# wfp_connector.net
KiCad netlist of a schematic drawn in Altium Designer
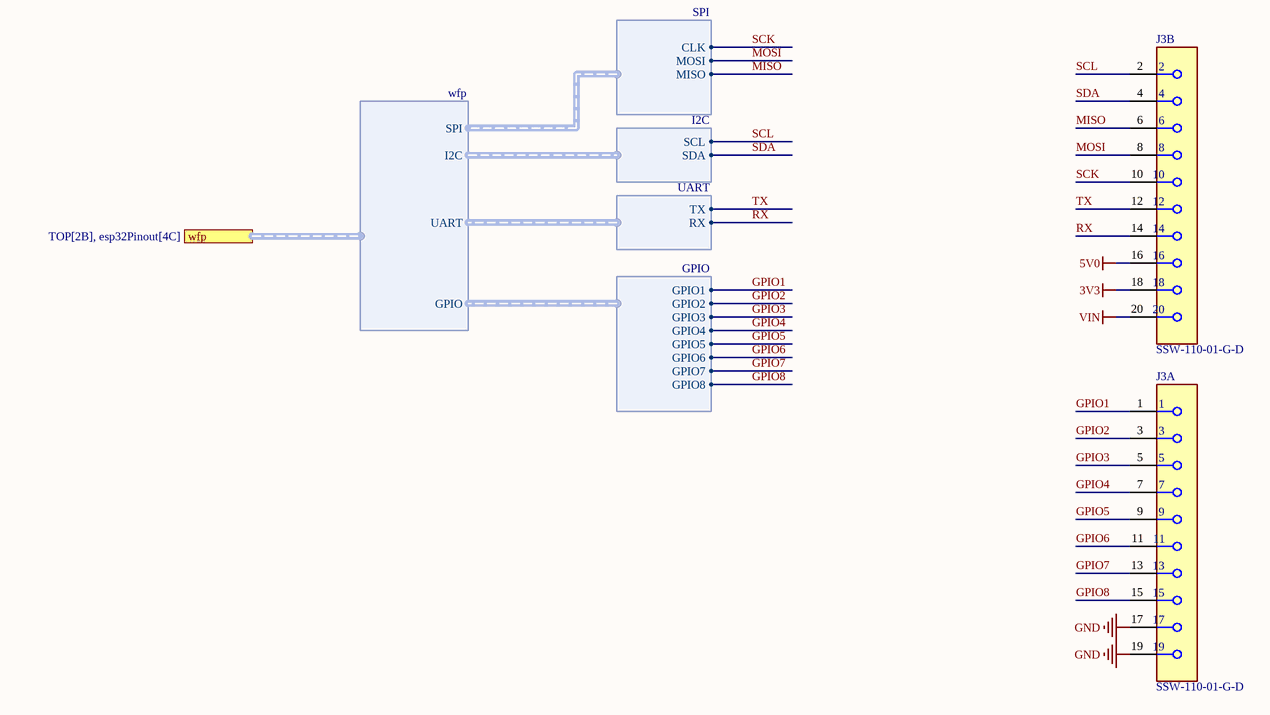
[diagram p0: wfp connector.SchDoc]

(export (version "E")
  (design (tool "Eeschema 10.0.6"))
  (components
    (comp (ref "J3")
      (value "SSW-110-01-G-D")
      (footprint "FP-SSW-110-01-G-D-MFG")
      (description "CONN RCPT 20POS 0.1 GOLD PCB")
      (libsource (lib "Altium Content Vault") (part "567498f665bc4df916ae72b6c86215c"))
    )
  )
  (nets
    (net (code "6") (name "/GPIO1") (class "Default")
      (node (ref "J3") (pin "1") (pinfunction "1_1") (pintype "passive"))
    )
    (net (code "7") (name "/GPIO2") (class "Default")
      (node (ref "J3") (pin "3") (pinfunction "3_3") (pintype "passive"))
    )
    (net (code "8") (name "/GPIO3") (class "Default")
      (node (ref "J3") (pin "5") (pinfunction "5_5") (pintype "passive"))
    )
    (net (code "9") (name "/GPIO4") (class "Default")
      (node (ref "J3") (pin "7") (pinfunction "7_7") (pintype "passive"))
    )
    (net (code "10") (name "/GPIO5") (class "Default")
      (node (ref "J3") (pin "9") (pinfunction "9_9") (pintype "passive"))
    )
    (net (code "11") (name "/GPIO6") (class "Default")
      (node (ref "J3") (pin "11") (pinfunction "11_11") (pintype "passive"))
    )
    (net (code "12") (name "/GPIO7") (class "Default")
      (node (ref "J3") (pin "13") (pinfunction "13_13") (pintype "passive"))
    )
    (net (code "13") (name "/GPIO8") (class "Default")
      (node (ref "J3") (pin "15") (pinfunction "15_15") (pintype "passive"))
    )
    (net (code "14") (name "/MISO") (class "Default")
      (node (ref "J3") (pin "6") (pinfunction "6_6") (pintype "passive"))
    )
    (net (code "15") (name "/MOSI") (class "Default")
      (node (ref "J3") (pin "8") (pinfunction "8_8") (pintype "passive"))
    )
    (net (code "16") (name "/RX") (class "Default")
      (node (ref "J3") (pin "14") (pinfunction "14_14") (pintype "passive"))
    )
    (net (code "17") (name "/SCK") (class "Default")
      (node (ref "J3") (pin "10") (pinfunction "10_10") (pintype "passive"))
    )
    (net (code "18") (name "/SCL") (class "Default")
      (node (ref "J3") (pin "2") (pinfunction "2_2") (pintype "passive"))
    )
    (net (code "19") (name "/SDA") (class "Default")
      (node (ref "J3") (pin "4") (pinfunction "4_4") (pintype "passive"))
    )
    (net (code "20") (name "/TX") (class "Default")
      (node (ref "J3") (pin "12") (pinfunction "12_12") (pintype "passive"))
    )
    (net (code "26") (name "3V3") (class "Default")
      (node (ref "J3") (pin "18") (pinfunction "18_18") (pintype "passive"))
    )
    (net (code "27") (name "5V0") (class "Default")
      (node (ref "J3") (pin "16") (pinfunction "16_16") (pintype "passive"))
    )
    (net (code "28") (name "GND") (class "Default")
      (node (ref "J3") (pin "17") (pinfunction "17_17") (pintype "passive"))
      (node (ref "J3") (pin "19") (pinfunction "19_19") (pintype "passive"))
    )
    (net (code "29") (name "VIN") (class "Default")
      (node (ref "J3") (pin "20") (pinfunction "20_20") (pintype "passive"))
    )
  )
)
